# Badge_V2.net
KiCad netlist of a schematic drawn in Altium Designer
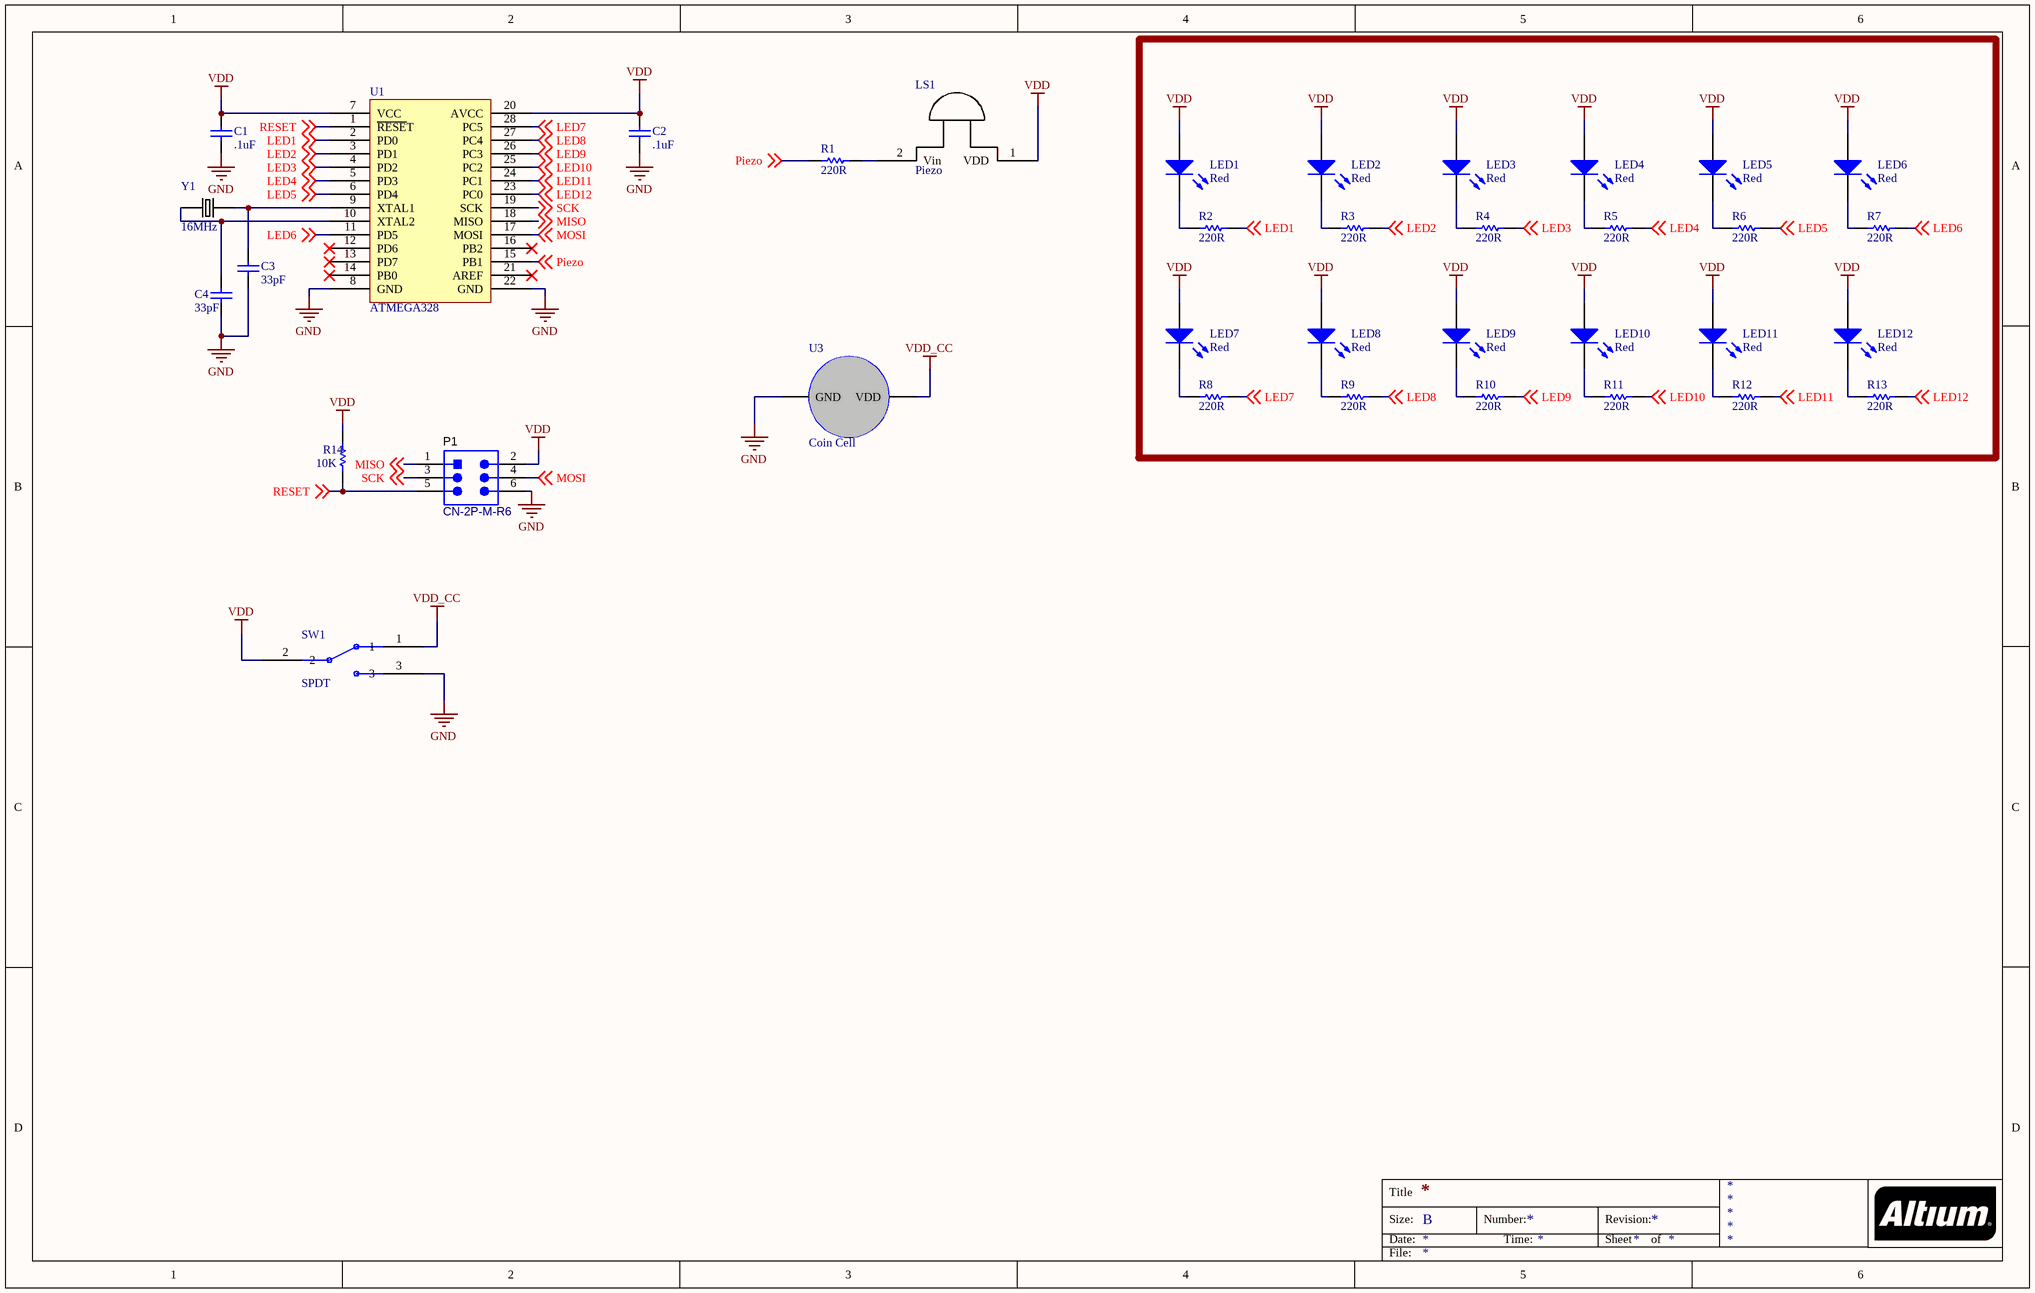
[diagram p0: Badge_V2.SchDoc]

(export (version "E")
  (design (tool "Eeschema 10.0.6"))
  (components
    (comp (ref "C1")
      (value ".1uF")
      (footprint "CAPC0805(2012)145_L")
      (description "capacitor")
      (fields (field (name "MANUFACTURER") "Yageo") (field (name "MPN") "CC0805ZRY5V9BB104"))
      (libsource (lib "Badge_V2") (part "CAP100n"))
    )
    (comp (ref "C2")
      (value ".1uF")
      (footprint "CAPC0805(2012)145_L")
      (description "capacitor")
      (fields (field (name "MANUFACTURER") "Yageo") (field (name "MPN") "CC0805ZRY5V9BB104"))
      (libsource (lib "Badge_V2") (part "CAP100n"))
    )
    (comp (ref "C3")
      (value "33pF")
      (footprint "CAPC0805(2012)145_L")
      (description "capacitor")
      (fields (field (name "MANUFACTURER") "Yageo") (field (name "MPN") "CC0805JRNPO9BN330"))
      (libsource (lib "Badge_V2") (part "CAP33p"))
    )
    (comp (ref "C4")
      (value "33pF")
      (footprint "CAPC0805(2012)145_L")
      (description "capacitor")
      (fields (field (name "MANUFACTURER") "Yageo") (field (name "MPN") "CC0805JRNPO9BN330"))
      (libsource (lib "Badge_V2") (part "CAP33p"))
    )
    (comp (ref "LED1")
      (value "Red")
      (footprint "LED_0805")
      (description "Red 625nm LED Indication - Discrete 2V 0805 (2012 Metric)")
      (fields (field (name "MPN") "150080RS75000") (field (name "MANUFACTURER") "Würth Elektronik"))
      (libsource (lib "Badge_V2") (part "LED_0805"))
    )
    (comp (ref "LED2")
      (value "Red")
      (footprint "LED_0805")
      (description "Red 625nm LED Indication - Discrete 2V 0805 (2012 Metric)")
      (fields (field (name "MPN") "150080RS75000") (field (name "MANUFACTURER") "Würth Elektronik"))
      (libsource (lib "Badge_V2") (part "LED_0805"))
    )
    (comp (ref "LED3")
      (value "Red")
      (footprint "LED_0805")
      (description "Red 625nm LED Indication - Discrete 2V 0805 (2012 Metric)")
      (fields (field (name "MPN") "150080RS75000") (field (name "MANUFACTURER") "Würth Elektronik"))
      (libsource (lib "Badge_V2") (part "LED_0805"))
    )
    (comp (ref "LED4")
      (value "Red")
      (footprint "LED_0805")
      (description "Red 625nm LED Indication - Discrete 2V 0805 (2012 Metric)")
      (fields (field (name "MPN") "150080RS75000") (field (name "MANUFACTURER") "Würth Elektronik"))
      (libsource (lib "Badge_V2") (part "LED_0805"))
    )
    (comp (ref "LED5")
      (value "Red")
      (footprint "LED_0805")
      (description "Red 625nm LED Indication - Discrete 2V 0805 (2012 Metric)")
      (fields (field (name "MPN") "150080RS75000") (field (name "MANUFACTURER") "Würth Elektronik"))
      (libsource (lib "Badge_V2") (part "LED_0805"))
    )
    (comp (ref "LED6")
      (value "Red")
      (footprint "LED_0805")
      (description "Red 625nm LED Indication - Discrete 2V 0805 (2012 Metric)")
      (fields (field (name "MPN") "150080RS75000") (field (name "MANUFACTURER") "Würth Elektronik"))
      (libsource (lib "Badge_V2") (part "LED_0805"))
    )
    (comp (ref "LED7")
      (value "Red")
      (footprint "LED_0805")
      (description "Red 625nm LED Indication - Discrete 2V 0805 (2012 Metric)")
      (fields (field (name "MPN") "150080RS75000") (field (name "MANUFACTURER") "Würth Elektronik"))
      (libsource (lib "Badge_V2") (part "LED_0805"))
    )
    (comp (ref "LED8")
      (value "Red")
      (footprint "LED_0805")
      (description "Red 625nm LED Indication - Discrete 2V 0805 (2012 Metric)")
      (fields (field (name "MPN") "150080RS75000") (field (name "MANUFACTURER") "Würth Elektronik"))
      (libsource (lib "Badge_V2") (part "LED_0805"))
    )
    (comp (ref "LED9")
      (value "Red")
      (footprint "LED_0805")
      (description "Red 625nm LED Indication - Discrete 2V 0805 (2012 Metric)")
      (fields (field (name "MPN") "150080RS75000") (field (name "MANUFACTURER") "Würth Elektronik"))
      (libsource (lib "Badge_V2") (part "LED_0805"))
    )
    (comp (ref "LED10")
      (value "Red")
      (footprint "LED_0805")
      (description "Red 625nm LED Indication - Discrete 2V 0805 (2012 Metric)")
      (fields (field (name "MPN") "150080RS75000") (field (name "MANUFACTURER") "Würth Elektronik"))
      (libsource (lib "Badge_V2") (part "LED_0805"))
    )
    (comp (ref "LED11")
      (value "Red")
      (footprint "LED_0805")
      (description "Red 625nm LED Indication - Discrete 2V 0805 (2012 Metric)")
      (fields (field (name "MPN") "150080RS75000") (field (name "MANUFACTURER") "Würth Elektronik"))
      (libsource (lib "Badge_V2") (part "LED_0805"))
    )
    (comp (ref "LED12")
      (value "Red")
      (footprint "LED_0805")
      (description "Red 625nm LED Indication - Discrete 2V 0805 (2012 Metric)")
      (fields (field (name "MPN") "150080RS75000") (field (name "MANUFACTURER") "Würth Elektronik"))
      (libsource (lib "Badge_V2") (part "LED_0805"))
    )
    (comp (ref "LS1")
      (value "Piezo")
      (footprint "Piezo")
      (description "AUDIO PIEZO TRANSDUCER 30V TH")
      (fields (field (name "MPN") "PS1240P02BT") (field (name "MANUFACTURER") "TDK Corporation"))
      (libsource (lib "Badge_V2") (part "Piezo"))
    )
    (comp (ref "P1")
      (value "CN-2P-M-R6")
      (footprint "HRWN-M20-9980346_V")
      (libsource (lib "Badge_V2") (part "CN-2P-M-R6"))
    )
    (comp (ref "R1")
      (value "220R")
      (footprint "RESC0805(2012)_M")
      (description "resistor")
      (fields (field (name "MANUFACTURER") "Yageo") (field (name "MPN") "RC0805JR-071KL"))
      (libsource (lib "Badge_V2") (part "RES"))
    )
    (comp (ref "R2")
      (value "220R")
      (footprint "RESC0805(2012)_M")
      (description "resistor")
      (fields (field (name "MANUFACTURER") "Yageo") (field (name "MPN") "RC0805JR-071KL"))
      (libsource (lib "Badge_V2") (part "RES"))
    )
    (comp (ref "R3")
      (value "220R")
      (footprint "RESC0805(2012)_M")
      (description "resistor")
      (fields (field (name "MANUFACTURER") "Yageo") (field (name "MPN") "RC0805JR-071KL"))
      (libsource (lib "Badge_V2") (part "RES"))
    )
    (comp (ref "R4")
      (value "220R")
      (footprint "RESC0805(2012)_M")
      (description "resistor")
      (fields (field (name "MANUFACTURER") "Yageo") (field (name "MPN") "RC0805JR-071KL"))
      (libsource (lib "Badge_V2") (part "RES"))
    )
    (comp (ref "R5")
      (value "220R")
      (footprint "RESC0805(2012)_M")
      (description "resistor")
      (fields (field (name "MANUFACTURER") "Yageo") (field (name "MPN") "RC0805JR-071KL"))
      (libsource (lib "Badge_V2") (part "RES"))
    )
    (comp (ref "R6")
      (value "220R")
      (footprint "RESC0805(2012)_M")
      (description "resistor")
      (fields (field (name "MANUFACTURER") "Yageo") (field (name "MPN") "RC0805JR-071KL"))
      (libsource (lib "Badge_V2") (part "RES"))
    )
    (comp (ref "R7")
      (value "220R")
      (footprint "RESC0805(2012)_M")
      (description "resistor")
      (fields (field (name "MANUFACTURER") "Yageo") (field (name "MPN") "RC0805JR-071KL"))
      (libsource (lib "Badge_V2") (part "RES"))
    )
    (comp (ref "R8")
      (value "220R")
      (footprint "RESC0805(2012)_M")
      (description "resistor")
      (fields (field (name "MANUFACTURER") "Yageo") (field (name "MPN") "RC0805JR-071KL"))
      (libsource (lib "Badge_V2") (part "RES"))
    )
    (comp (ref "R9")
      (value "220R")
      (footprint "RESC0805(2012)_M")
      (description "resistor")
      (fields (field (name "MANUFACTURER") "Yageo") (field (name "MPN") "RC0805JR-071KL"))
      (libsource (lib "Badge_V2") (part "RES"))
    )
    (comp (ref "R10")
      (value "220R")
      (footprint "RESC0805(2012)_M")
      (description "resistor")
      (fields (field (name "MANUFACTURER") "Yageo") (field (name "MPN") "RC0805JR-071KL"))
      (libsource (lib "Badge_V2") (part "RES"))
    )
    (comp (ref "R11")
      (value "220R")
      (footprint "RESC0805(2012)_M")
      (description "resistor")
      (fields (field (name "MANUFACTURER") "Yageo") (field (name "MPN") "RC0805JR-071KL"))
      (libsource (lib "Badge_V2") (part "RES"))
    )
    (comp (ref "R12")
      (value "220R")
      (footprint "RESC0805(2012)_M")
      (description "resistor")
      (fields (field (name "MANUFACTURER") "Yageo") (field (name "MPN") "RC0805JR-071KL"))
      (libsource (lib "Badge_V2") (part "RES"))
    )
    (comp (ref "R13")
      (value "220R")
      (footprint "RESC0805(2012)_M")
      (description "resistor")
      (fields (field (name "MANUFACTURER") "Yageo") (field (name "MPN") "RC0805JR-071KL"))
      (libsource (lib "Badge_V2") (part "RES"))
    )
    (comp (ref "R14")
      (value "10K")
      (footprint "RESC0805(2012)_M")
      (description "resistor")
      (fields (field (name "MANUFACTURER") "Yageo") (field (name "MPN") "RC0603JR-0710KL"))
      (libsource (lib "Badge_V2") (part "RES10K"))
    )
    (comp (ref "SW1")
      (value "SPDT")
      (footprint "EG1218_EG1218")
      (description "Slide Switch SPDT Through Hole")
      (fields (field (name "MPN") "EG1218") (field (name "MANUFACTURER") "E-Switch"))
      (libsource (lib "Badge_V2") (part "SPDT_Switch"))
    )
    (comp (ref "U1")
      (value "ATMEGA328")
      (footprint "1-2199298-9")
      (description "AVR AVR® ATmega Microcontroller IC 8-Bit 20MHz 32KB (16K x 16) FLASH 28-PDIP")
      (fields (field (name "MANUFACTURER") "Microchip Technology") (field (name "MPN") "ATMEGA328-PU"))
      (libsource (lib "Badge_V2") (part "ATMEGA328-PU"))
    )
    (comp (ref "U3")
      (value "Coin Cell")
      (footprint "Batt")
      (description "Battery Retainer Coin, 20.0mm 1 Cell SMD (SMT) Tab")
      (fields (field (name "MPN") "3034TR") (field (name "MANUFACTURER") "Keystone Electronics"))
      (libsource (lib "badge") (part "Batt"))
    )
    (comp (ref "Y1")
      (value "16MHz")
      (footprint "XTAL_ECS-160-20-3X-TR")
      (description "16MHz Â±30ppm Crystal 20pF 50 Ohms HC-49/US")
      (fields (field (name "MANUFACTURER") "ECS Inc.") (field (name "MPN") "ECS-160-20-3X-TR"))
      (libsource (lib "Badge_V2") (part "ECS-160-20-3X-TR"))
    )
  )
  (nets
    (net (code "1") (name "GND") (class "Default")
      (node (ref "C1") (pin "1") (pinfunction "1_1") (pintype "passive"))
      (node (ref "C2") (pin "1") (pinfunction "1_1") (pintype "passive"))
      (node (ref "C3") (pin "1") (pinfunction "1_1") (pintype "passive"))
      (node (ref "C4") (pin "1") (pinfunction "1_1") (pintype "passive"))
      (node (ref "P1") (pin "6") (pinfunction "6_6") (pintype "passive"))
      (node (ref "SW1") (pin "3") (pinfunction "3_3") (pintype "passive"))
      (node (ref "U1") (pin "22") (pinfunction "GND_22") (pintype "passive"))
      (node (ref "U1") (pin "8") (pinfunction "GND_8") (pintype "passive"))
      (node (ref "U3") (pin "GND") (pinfunction "GND_GND") (pintype "passive"))
    )
    (net (code "2") (name "LED1") (class "Default")
      (node (ref "R2") (pin "2") (pinfunction "2_2") (pintype "passive"))
      (node (ref "U1") (pin "2") (pinfunction "PD0_2") (pintype "passive"))
    )
    (net (code "3") (name "LED2") (class "Default")
      (node (ref "R3") (pin "2") (pinfunction "2_2") (pintype "passive"))
      (node (ref "U1") (pin "3") (pinfunction "PD1_3") (pintype "passive"))
    )
    (net (code "4") (name "LED3") (class "Default")
      (node (ref "R4") (pin "2") (pinfunction "2_2") (pintype "passive"))
      (node (ref "U1") (pin "4") (pinfunction "PD2_4") (pintype "passive"))
    )
    (net (code "5") (name "LED4") (class "Default")
      (node (ref "R5") (pin "2") (pinfunction "2_2") (pintype "passive"))
      (node (ref "U1") (pin "5") (pinfunction "PD3_5") (pintype "passive"))
    )
    (net (code "6") (name "LED5") (class "Default")
      (node (ref "R6") (pin "2") (pinfunction "2_2") (pintype "passive"))
      (node (ref "U1") (pin "6") (pinfunction "PD4_6") (pintype "passive"))
    )
    (net (code "7") (name "LED6") (class "Default")
      (node (ref "R7") (pin "2") (pinfunction "2_2") (pintype "passive"))
      (node (ref "U1") (pin "11") (pinfunction "PD5_11") (pintype "passive"))
    )
    (net (code "8") (name "LED7") (class "Default")
      (node (ref "R8") (pin "2") (pinfunction "2_2") (pintype "passive"))
      (node (ref "U1") (pin "28") (pinfunction "PC5_28") (pintype "passive"))
    )
    (net (code "9") (name "LED8") (class "Default")
      (node (ref "R9") (pin "2") (pinfunction "2_2") (pintype "passive"))
      (node (ref "U1") (pin "27") (pinfunction "PC4_27") (pintype "passive"))
    )
    (net (code "10") (name "LED9") (class "Default")
      (node (ref "R10") (pin "2") (pinfunction "2_2") (pintype "passive"))
      (node (ref "U1") (pin "26") (pinfunction "PC3_26") (pintype "passive"))
    )
    (net (code "11") (name "LED10") (class "Default")
      (node (ref "R11") (pin "2") (pinfunction "2_2") (pintype "passive"))
      (node (ref "U1") (pin "25") (pinfunction "PC2_25") (pintype "passive"))
    )
    (net (code "12") (name "LED11") (class "Default")
      (node (ref "R12") (pin "2") (pinfunction "2_2") (pintype "passive"))
      (node (ref "U1") (pin "24") (pinfunction "PC1_24") (pintype "passive"))
    )
    (net (code "13") (name "LED12") (class "Default")
      (node (ref "R13") (pin "2") (pinfunction "2_2") (pintype "passive"))
      (node (ref "U1") (pin "23") (pinfunction "PC0_23") (pintype "passive"))
    )
    (net (code "14") (name "MISO") (class "Default")
      (node (ref "P1") (pin "1") (pinfunction "1_1") (pintype "passive"))
      (node (ref "U1") (pin "18") (pinfunction "MISO_18") (pintype "passive"))
    )
    (net (code "15") (name "MOSI") (class "Default")
      (node (ref "P1") (pin "4") (pinfunction "4_4") (pintype "passive"))
      (node (ref "U1") (pin "17") (pinfunction "MOSI_17") (pintype "passive"))
    )
    (net (code "16") (name "Net-(LED1-K)") (class "Default")
      (node (ref "LED1") (pin "1") (pinfunction "K_1") (pintype "passive"))
      (node (ref "R2") (pin "1") (pinfunction "1_1") (pintype "passive"))
    )
    (net (code "17") (name "Net-(LED2-K)") (class "Default")
      (node (ref "LED2") (pin "1") (pinfunction "K_1") (pintype "passive"))
      (node (ref "R3") (pin "1") (pinfunction "1_1") (pintype "passive"))
    )
    (net (code "18") (name "Net-(LED3-K)") (class "Default")
      (node (ref "LED3") (pin "1") (pinfunction "K_1") (pintype "passive"))
      (node (ref "R4") (pin "1") (pinfunction "1_1") (pintype "passive"))
    )
    (net (code "19") (name "Net-(LED4-K)") (class "Default")
      (node (ref "LED4") (pin "1") (pinfunction "K_1") (pintype "passive"))
      (node (ref "R5") (pin "1") (pinfunction "1_1") (pintype "passive"))
    )
    (net (code "20") (name "Net-(LED5-K)") (class "Default")
      (node (ref "LED5") (pin "1") (pinfunction "K_1") (pintype "passive"))
      (node (ref "R6") (pin "1") (pinfunction "1_1") (pintype "passive"))
    )
    (net (code "21") (name "Net-(LED6-K)") (class "Default")
      (node (ref "LED6") (pin "1") (pinfunction "K_1") (pintype "passive"))
      (node (ref "R7") (pin "1") (pinfunction "1_1") (pintype "passive"))
    )
    (net (code "22") (name "Net-(LED7-K)") (class "Default")
      (node (ref "LED7") (pin "1") (pinfunction "K_1") (pintype "passive"))
      (node (ref "R8") (pin "1") (pinfunction "1_1") (pintype "passive"))
    )
    (net (code "23") (name "Net-(LED8-K)") (class "Default")
      (node (ref "LED8") (pin "1") (pinfunction "K_1") (pintype "passive"))
      (node (ref "R9") (pin "1") (pinfunction "1_1") (pintype "passive"))
    )
    (net (code "24") (name "Net-(LED9-K)") (class "Default")
      (node (ref "LED9") (pin "1") (pinfunction "K_1") (pintype "passive"))
      (node (ref "R10") (pin "1") (pinfunction "1_1") (pintype "passive"))
    )
    (net (code "25") (name "Net-(LED10-K)") (class "Default")
      (node (ref "LED10") (pin "1") (pinfunction "K_1") (pintype "passive"))
      (node (ref "R11") (pin "1") (pinfunction "1_1") (pintype "passive"))
    )
    (net (code "26") (name "Net-(LED11-K)") (class "Default")
      (node (ref "LED11") (pin "1") (pinfunction "K_1") (pintype "passive"))
      (node (ref "R12") (pin "1") (pinfunction "1_1") (pintype "passive"))
    )
    (net (code "27") (name "Net-(LED12-K)") (class "Default")
      (node (ref "LED12") (pin "1") (pinfunction "K_1") (pintype "passive"))
      (node (ref "R13") (pin "1") (pinfunction "1_1") (pintype "passive"))
    )
    (net (code "28") (name "Net-(LS1-Vin)") (class "Default")
      (node (ref "LS1") (pin "2") (pinfunction "Vin_2") (pintype "passive"))
      (node (ref "R1") (pin "2") (pinfunction "2_2") (pintype "passive"))
    )
    (net (code "29") (name "Net-(U1-XTAL1)") (class "Default")
      (node (ref "C3") (pin "2") (pinfunction "2_2") (pintype "passive"))
      (node (ref "U1") (pin "9") (pinfunction "XTAL1_9") (pintype "passive"))
      (node (ref "Y1") (pin "2") (pinfunction "2_2") (pintype "passive"))
    )
    (net (code "30") (name "Net-(U1-XTAL2)") (class "Default")
      (node (ref "C4") (pin "2") (pinfunction "2_2") (pintype "passive"))
      (node (ref "U1") (pin "10") (pinfunction "XTAL2_10") (pintype "passive"))
      (node (ref "Y1") (pin "1") (pinfunction "1_1") (pintype "passive"))
    )
    (net (code "31") (name "Piezo") (class "Default")
      (node (ref "R1") (pin "1") (pinfunction "1_1") (pintype "passive"))
      (node (ref "U1") (pin "15") (pinfunction "PB1_15") (pintype "passive"))
    )
    (net (code "32") (name "RESET") (class "Default")
      (node (ref "P1") (pin "5") (pinfunction "5_5") (pintype "passive"))
      (node (ref "R14") (pin "2") (pinfunction "2_2") (pintype "passive"))
      (node (ref "U1") (pin "1") (pinfunction "~{RESE}T_1") (pintype "passive"))
    )
    (net (code "33") (name "SCK") (class "Default")
      (node (ref "P1") (pin "3") (pinfunction "3_3") (pintype "passive"))
      (node (ref "U1") (pin "19") (pinfunction "SCK_19") (pintype "passive"))
    )
    (net (code "34") (name "VDD") (class "Default")
      (node (ref "C1") (pin "2") (pinfunction "2_2") (pintype "passive"))
      (node (ref "C2") (pin "2") (pinfunction "2_2") (pintype "passive"))
      (node (ref "LED1") (pin "2") (pinfunction "A_2") (pintype "passive"))
      (node (ref "LED10") (pin "2") (pinfunction "A_2") (pintype "passive"))
      (node (ref "LED11") (pin "2") (pinfunction "A_2") (pintype "passive"))
      (node (ref "LED12") (pin "2") (pinfunction "A_2") (pintype "passive"))
      (node (ref "LED2") (pin "2") (pinfunction "A_2") (pintype "passive"))
      (node (ref "LED3") (pin "2") (pinfunction "A_2") (pintype "passive"))
      (node (ref "LED4") (pin "2") (pinfunction "A_2") (pintype "passive"))
      (node (ref "LED5") (pin "2") (pinfunction "A_2") (pintype "passive"))
      (node (ref "LED6") (pin "2") (pinfunction "A_2") (pintype "passive"))
      (node (ref "LED7") (pin "2") (pinfunction "A_2") (pintype "passive"))
      (node (ref "LED8") (pin "2") (pinfunction "A_2") (pintype "passive"))
      (node (ref "LED9") (pin "2") (pinfunction "A_2") (pintype "passive"))
      (node (ref "LS1") (pin "1") (pinfunction "VDD_1") (pintype "passive"))
      (node (ref "P1") (pin "2") (pinfunction "2_2") (pintype "passive"))
      (node (ref "R14") (pin "1") (pinfunction "1_1") (pintype "passive"))
      (node (ref "SW1") (pin "2") (pinfunction "2_2") (pintype "passive"))
      (node (ref "U1") (pin "20") (pinfunction "AVCC_20") (pintype "passive"))
      (node (ref "U1") (pin "7") (pinfunction "VCC_7") (pintype "passive"))
    )
    (net (code "35") (name "VDD_CC") (class "Default")
      (node (ref "SW1") (pin "1") (pinfunction "1_1") (pintype "passive"))
      (node (ref "U3") (pin "VDD") (pinfunction "VDD_VDD") (pintype "passive"))
    )
    (net (code "36") (name "unconnected-(U1-AREF-Pad21)") (class "Default")
      (node (ref "U1") (pin "21") (pinfunction "AREF_21") (pintype "passive+no_connect"))
    )
    (net (code "37") (name "unconnected-(U1-PB0-Pad14)") (class "Default")
      (node (ref "U1") (pin "14") (pinfunction "PB0_14") (pintype "passive+no_connect"))
    )
    (net (code "38") (name "unconnected-(U1-PB2-Pad16)") (class "Default")
      (node (ref "U1") (pin "16") (pinfunction "PB2_16") (pintype "passive+no_connect"))
    )
    (net (code "39") (name "unconnected-(U1-PD6-Pad12)") (class "Default")
      (node (ref "U1") (pin "12") (pinfunction "PD6_12") (pintype "passive+no_connect"))
    )
    (net (code "40") (name "unconnected-(U1-PD7-Pad13)") (class "Default")
      (node (ref "U1") (pin "13") (pinfunction "PD7_13") (pintype "passive+no_connect"))
    )
  )
)
